# STM32H730_PINOUT.net
KiCad netlist of a schematic drawn in Altium Designer
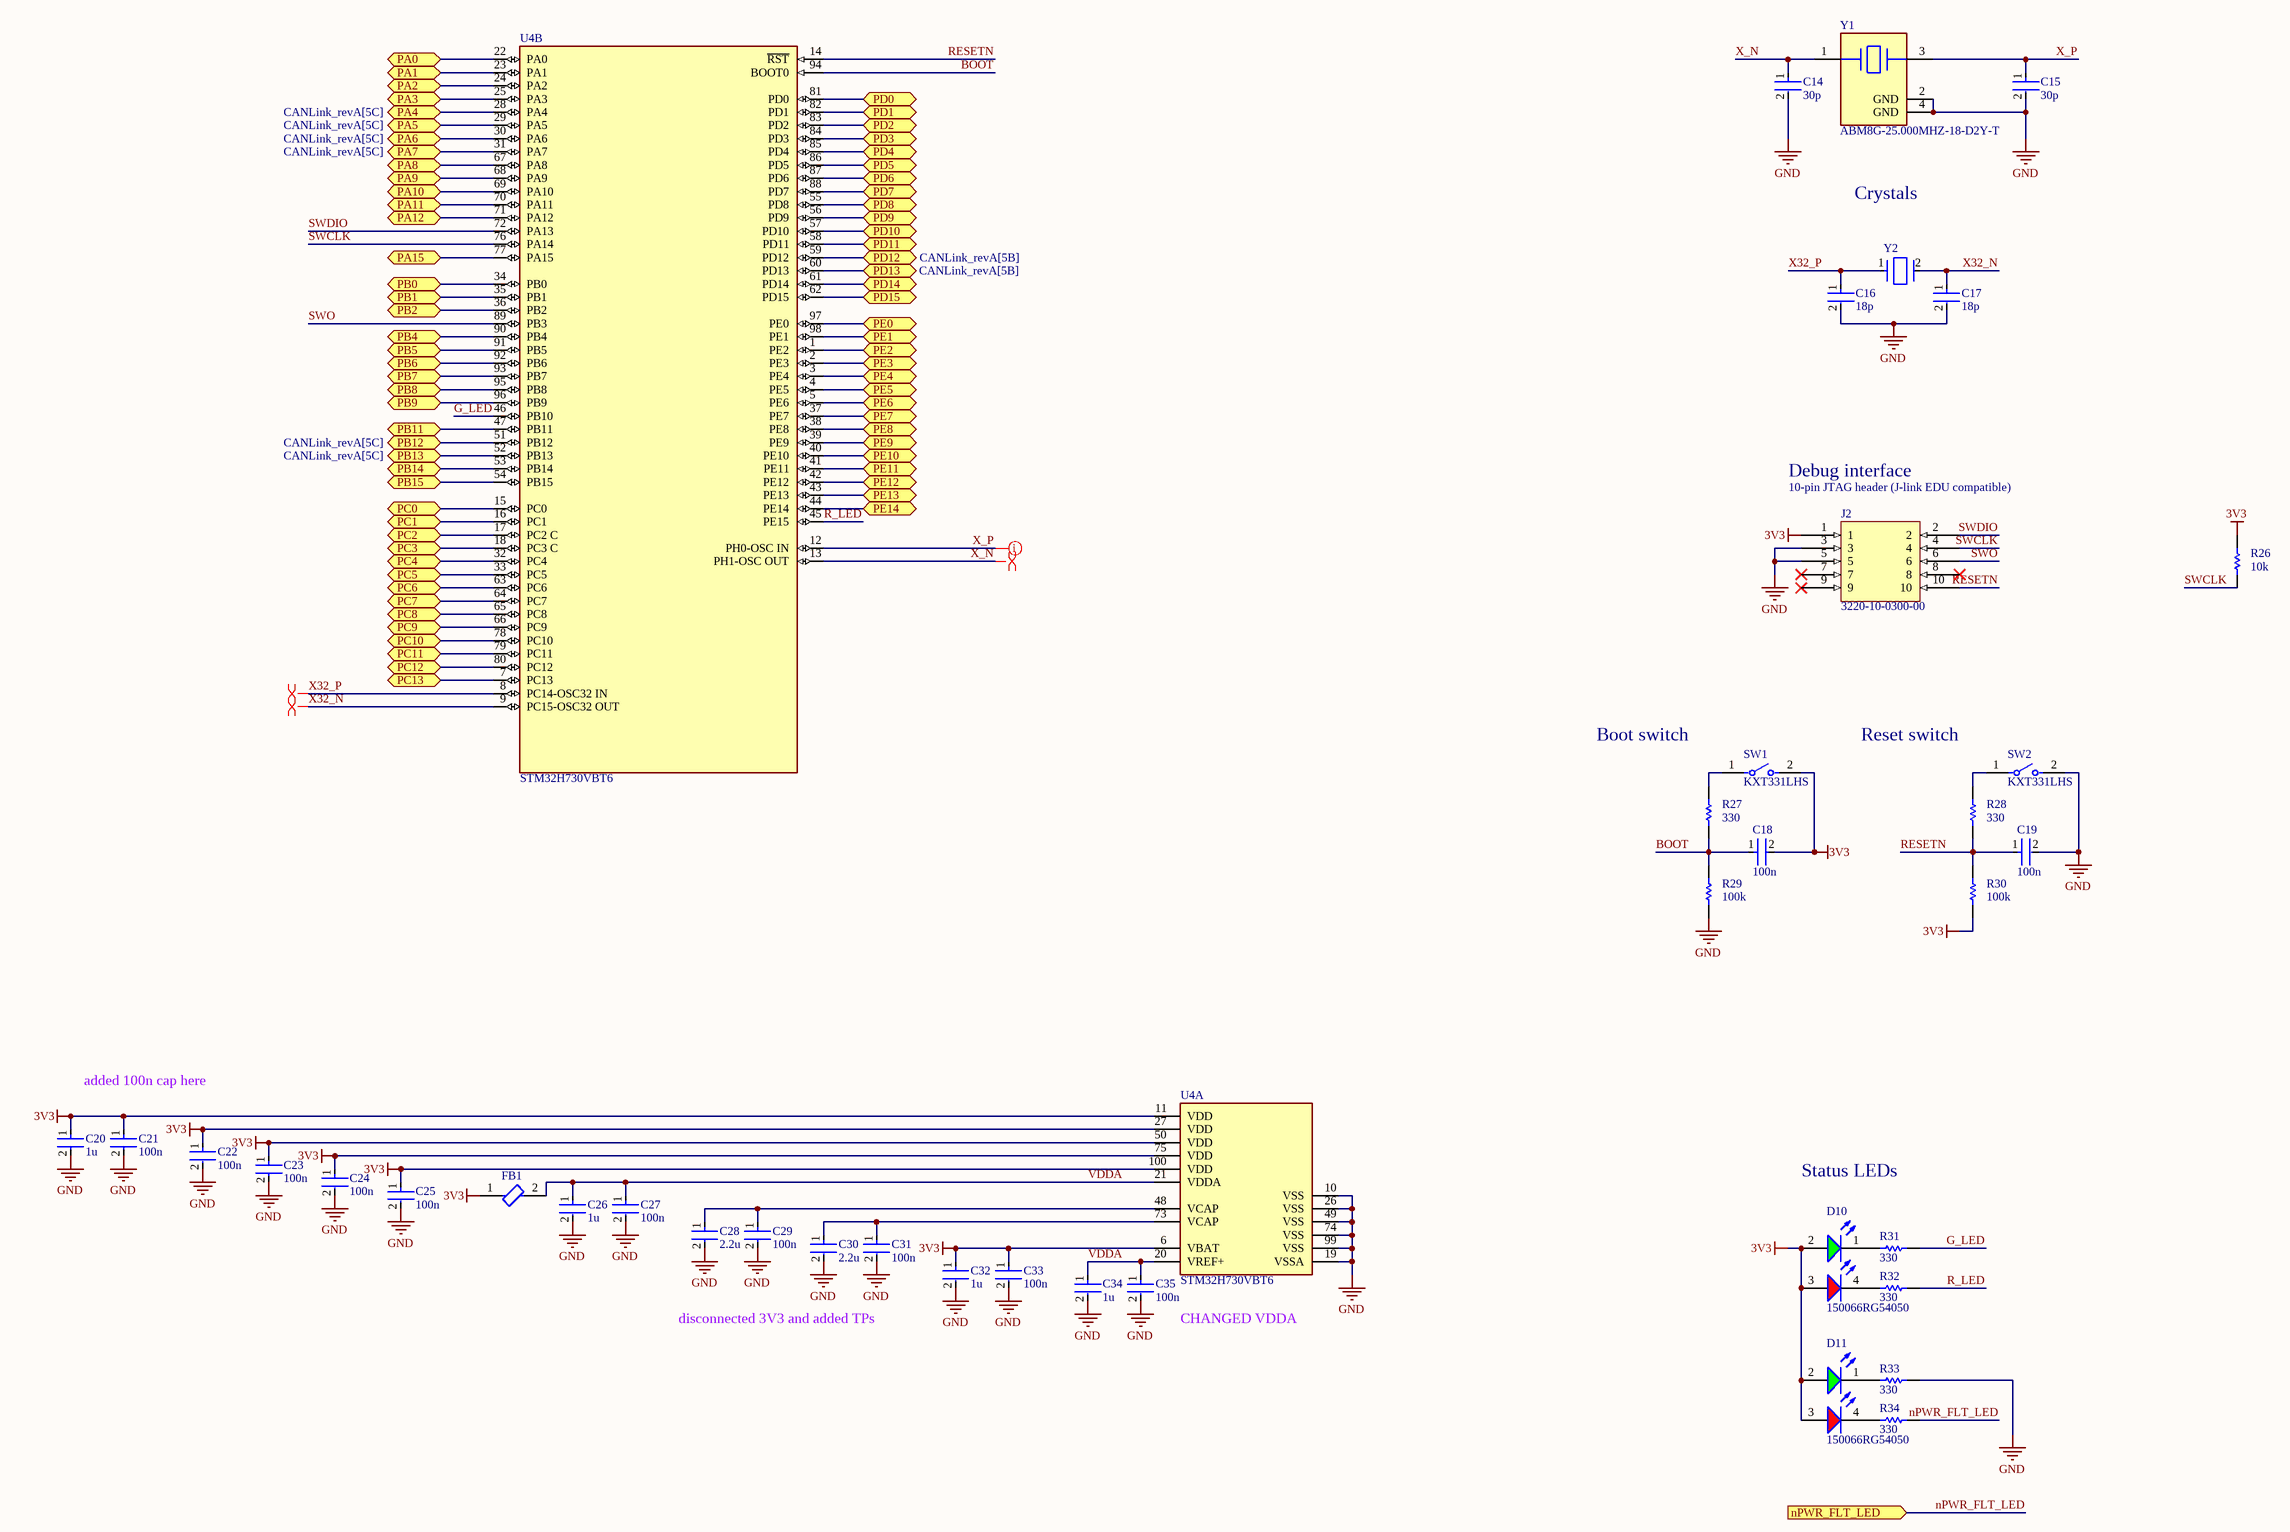
[diagram p0: STM32H730_PINOUT.SchDoc]

(export (version "E")
  (design (tool "Eeschema 10.0.6"))
  (components
    (comp (ref "C14")
      (value "30p")
      (footprint "FP-0402-L_1_0_0_05-W_0_5-IPC_A")
      (description "LARGE PADS, 0402 CAP, CHANGE COMMENT TO MATCH REAL P/N")
      (libsource (lib "Space Concordia") (part "b4654b650e69147ec39a6b967a45e02"))
    )
    (comp (ref "C15")
      (value "30p")
      (footprint "FP-0402-L_1_0_0_05-W_0_5-IPC_A")
      (description "LARGE PADS, 0402 CAP, CHANGE COMMENT TO MATCH REAL P/N")
      (libsource (lib "Space Concordia") (part "b4654b650e69147ec39a6b967a45e02"))
    )
    (comp (ref "C16")
      (value "18p")
      (footprint "FP-0402-L_1_0_0_05-W_0_5-IPC_A")
      (description "LARGE PADS, 0402 CAP, CHANGE COMMENT TO MATCH REAL P/N")
      (libsource (lib "Space Concordia") (part "b4654b650e69147ec39a6b967a45e02"))
    )
    (comp (ref "C17")
      (value "18p")
      (footprint "FP-0402-L_1_0_0_05-W_0_5-IPC_A")
      (description "LARGE PADS, 0402 CAP, CHANGE COMMENT TO MATCH REAL P/N")
      (libsource (lib "Space Concordia") (part "b4654b650e69147ec39a6b967a45e02"))
    )
    (comp (ref "C18")
      (value "100n")
      (footprint "FP-0402-L_1_0_0_05-W_0_5-IPC_A")
      (description "LARGE PADS, 0402 CAP, CHANGE COMMENT TO MATCH REAL P/N")
      (libsource (lib "Space Concordia") (part "b4654b650e69147ec39a6b967a45e02"))
    )
    (comp (ref "C19")
      (value "100n")
      (footprint "FP-0402-L_1_0_0_05-W_0_5-IPC_A")
      (description "LARGE PADS, 0402 CAP, CHANGE COMMENT TO MATCH REAL P/N")
      (libsource (lib "Space Concordia") (part "b4654b650e69147ec39a6b967a45e02"))
    )
    (comp (ref "C20")
      (value "1u")
      (footprint "FP-0402-L_1_0_0_05-W_0_5-IPC_A")
      (description "LARGE PADS, 0402 CAP, CHANGE COMMENT TO MATCH REAL P/N")
      (libsource (lib "Space Concordia") (part "b4654b650e69147ec39a6b967a45e02"))
    )
    (comp (ref "C21")
      (value "100n")
      (footprint "FP-0402-L_1_0_0_05-W_0_5-IPC_A")
      (description "LARGE PADS, 0402 CAP, CHANGE COMMENT TO MATCH REAL P/N")
      (libsource (lib "Space Concordia") (part "b4654b650e69147ec39a6b967a45e02"))
    )
    (comp (ref "C22")
      (value "100n")
      (footprint "FP-0402-L_1_0_0_05-W_0_5-IPC_A")
      (description "LARGE PADS, 0402 CAP, CHANGE COMMENT TO MATCH REAL P/N")
      (libsource (lib "Space Concordia") (part "b4654b650e69147ec39a6b967a45e02"))
    )
    (comp (ref "C23")
      (value "100n")
      (footprint "FP-0402-L_1_0_0_05-W_0_5-IPC_A")
      (description "LARGE PADS, 0402 CAP, CHANGE COMMENT TO MATCH REAL P/N")
      (libsource (lib "Space Concordia") (part "b4654b650e69147ec39a6b967a45e02"))
    )
    (comp (ref "C24")
      (value "100n")
      (footprint "FP-0402-L_1_0_0_05-W_0_5-IPC_A")
      (description "LARGE PADS, 0402 CAP, CHANGE COMMENT TO MATCH REAL P/N")
      (libsource (lib "Space Concordia") (part "b4654b650e69147ec39a6b967a45e02"))
    )
    (comp (ref "C25")
      (value "100n")
      (footprint "FP-0402-L_1_0_0_05-W_0_5-IPC_A")
      (description "LARGE PADS, 0402 CAP, CHANGE COMMENT TO MATCH REAL P/N")
      (libsource (lib "Space Concordia") (part "b4654b650e69147ec39a6b967a45e02"))
    )
    (comp (ref "C26")
      (value "1u")
      (footprint "FP-0402-L_1_0_0_05-W_0_5-IPC_A")
      (description "LARGE PADS, 0402 CAP, CHANGE COMMENT TO MATCH REAL P/N")
      (libsource (lib "Space Concordia") (part "b4654b650e69147ec39a6b967a45e02"))
    )
    (comp (ref "C27")
      (value "100n")
      (footprint "FP-0402-L_1_0_0_05-W_0_5-IPC_A")
      (description "LARGE PADS, 0402 CAP, CHANGE COMMENT TO MATCH REAL P/N")
      (libsource (lib "Space Concordia") (part "b4654b650e69147ec39a6b967a45e02"))
    )
    (comp (ref "C28")
      (value "2.2u")
      (footprint "FP-0402-L_1_0_0_05-W_0_5-IPC_A")
      (description "LARGE PADS, 0402 CAP, CHANGE COMMENT TO MATCH REAL P/N")
      (libsource (lib "Space Concordia") (part "b4654b650e69147ec39a6b967a45e02"))
    )
    (comp (ref "C29")
      (value "100n")
      (footprint "FP-0402-L_1_0_0_05-W_0_5-IPC_A")
      (description "LARGE PADS, 0402 CAP, CHANGE COMMENT TO MATCH REAL P/N")
      (libsource (lib "Space Concordia") (part "b4654b650e69147ec39a6b967a45e02"))
    )
    (comp (ref "C30")
      (value "2.2u")
      (footprint "FP-0402-L_1_0_0_05-W_0_5-IPC_A")
      (description "LARGE PADS, 0402 CAP, CHANGE COMMENT TO MATCH REAL P/N")
      (libsource (lib "Space Concordia") (part "b4654b650e69147ec39a6b967a45e02"))
    )
    (comp (ref "C31")
      (value "100n")
      (footprint "FP-0402-L_1_0_0_05-W_0_5-IPC_A")
      (description "LARGE PADS, 0402 CAP, CHANGE COMMENT TO MATCH REAL P/N")
      (libsource (lib "Space Concordia") (part "b4654b650e69147ec39a6b967a45e02"))
    )
    (comp (ref "C32")
      (value "1u")
      (footprint "FP-0402-L_1_0_0_05-W_0_5-IPC_A")
      (description "LARGE PADS, 0402 CAP, CHANGE COMMENT TO MATCH REAL P/N")
      (libsource (lib "Space Concordia") (part "b4654b650e69147ec39a6b967a45e02"))
    )
    (comp (ref "C33")
      (value "100n")
      (footprint "FP-0402-L_1_0_0_05-W_0_5-IPC_A")
      (description "LARGE PADS, 0402 CAP, CHANGE COMMENT TO MATCH REAL P/N")
      (libsource (lib "Space Concordia") (part "b4654b650e69147ec39a6b967a45e02"))
    )
    (comp (ref "C34")
      (value "1u")
      (footprint "FP-0402-L_1_0_0_05-W_0_5-IPC_A")
      (description "LARGE PADS, 0402 CAP, CHANGE COMMENT TO MATCH REAL P/N")
      (libsource (lib "Space Concordia") (part "b4654b650e69147ec39a6b967a45e02"))
    )
    (comp (ref "C35")
      (value "100n")
      (footprint "FP-0402-L_1_0_0_05-W_0_5-IPC_A")
      (description "LARGE PADS, 0402 CAP, CHANGE COMMENT TO MATCH REAL P/N")
      (libsource (lib "Space Concordia") (part "b4654b650e69147ec39a6b967a45e02"))
    )
    (comp (ref "D10")
      (value "150066RG54050")
      (footprint "WL-SBCD_0606")
      (description "Led, Red/Grn, 180Mcd/230Mcd, 624Nm/525Nm Rohs Compliant: Yes")
      (fields (field (name "SOURCE") "rgled.SchLib"))
      (libsource (lib "Space Concordia") (part "CMP-004-00034-2"))
    )
    (comp (ref "D11")
      (value "150066RG54050")
      (footprint "WL-SBCD_0606")
      (description "Led, Red/Grn, 180Mcd/230Mcd, 624Nm/525Nm Rohs Compliant: Yes")
      (fields (field (name "SOURCE") "rgled.SchLib"))
      (libsource (lib "Space Concordia") (part "CMP-004-00034-2"))
    )
    (comp (ref "FB1")
      (value "BLM15PX601SN1D")
      (footprint "FP-BLM15-0_05-IPC_A")
      (description "Chip Ferrite Bead, 0402, 600Ω @ 100MHz, 0.23Ω, 25%, 900mA")
      (fields (field (name "TOLERANCE") "25%"))
      (libsource (lib "Altium Content Vault") (part "5f30dd21d616792df468990f7003faa"))
    )
    (comp (ref "J2")
      (value "3220-10-0300-00")
      (footprint "3220-10-0300-00-Footprint-1")
      (description "CONN HEADER SMD 10POS 1.27MM")
      (libsource (lib "Space Concordia") (part "3220-10-0300-00"))
    )
    (comp (ref "R26")
      (value "10k")
      (footprint "R0603B")
      (description "Resistor")
      (libsource (lib "Space Concordia") (part "Resistor"))
    )
    (comp (ref "R27")
      (value "330")
      (footprint "R0603B")
      (description "Resistor")
      (libsource (lib "Space Concordia") (part "Resistor"))
    )
    (comp (ref "R28")
      (value "330")
      (footprint "R0603B")
      (description "Resistor")
      (libsource (lib "Space Concordia") (part "Resistor"))
    )
    (comp (ref "R29")
      (value "100k")
      (footprint "R0603B")
      (description "Resistor")
      (libsource (lib "Space Concordia") (part "Resistor"))
    )
    (comp (ref "R30")
      (value "100k")
      (footprint "R0603B")
      (description "Resistor")
      (libsource (lib "Space Concordia") (part "Resistor"))
    )
    (comp (ref "R31")
      (value "330")
      (footprint "R0603B")
      (description "Resistor")
      (libsource (lib "Space Concordia") (part "Resistor"))
    )
    (comp (ref "R32")
      (value "330")
      (footprint "R0603B")
      (description "Resistor")
      (libsource (lib "Space Concordia") (part "Resistor"))
    )
    (comp (ref "R33")
      (value "330")
      (footprint "R0603B")
      (description "Resistor")
      (libsource (lib "Space Concordia") (part "Resistor"))
    )
    (comp (ref "R34")
      (value "330")
      (footprint "R0603B")
      (description "Resistor")
      (libsource (lib "Space Concordia") (part "Resistor"))
    )
    (comp (ref "SW1")
      (value "KXT331LHS")
      (footprint "FP-KXT331LHS-MFG")
      (description "SWITCH TACTILE SPST-NO 0.02A 15V")
      (libsource (lib "Altium Content Vault") (part "bb27bde45df87f1f469753f287ef5ae"))
    )
    (comp (ref "SW2")
      (value "KXT331LHS")
      (footprint "FP-KXT331LHS-MFG")
      (description "SWITCH TACTILE SPST-NO 0.02A 15V")
      (libsource (lib "Altium Content Vault") (part "bb27bde45df87f1f469753f287ef5ae"))
    )
    (comp (ref "U4")
      (value "STM32H730VBT6")
      (footprint "FP-LQFP100-1L-IPC_C")
      (description "IC MCU 32BIT 128KB FLASH 100LQFP")
      (libsource (lib "Altium Content Vault") (part "44dc6501260a4d92b846760feb66c20"))
    )
    (comp (ref "Y1")
      (value "ABM8G-25.000MHZ-18-D2Y-T")
      (footprint "FP-ABM8G-MFG")
      (description "Crystal 25MHz ±20ppm (Tol) ±30ppm (Stability) 18pF FUND 60Ω 4-Pin SMD T/R")
      (fields (field (name "TOLERANCE") "20ppm"))
      (libsource (lib "Altium Content Vault") (part "48e526d86b7f2615d98721063c72f49"))
    )
    (comp (ref "Y2")
      (value "ECS-.327-12.5-1210-TR")
      (footprint "FP-ECX-1210-MFG")
      (description "CRYSTAL 32.7680KHZ 12.5PF SMD")
      (fields
        (field (name "OCTOPART") "https://octopart.com/ecs-.327-12.5-1210-tr-ecs+international-81221340")
        (field (name "TOLERANCE") "20ppm")
      )
      (libsource (lib "Altium Content Vault") (part "99724985039315a44fd0d1401b84e49"))
    )
  )
  (nets
    (net (code "1") (name "/BOOT") (class "Default")
      (node (ref "C18") (pin "1") (pinfunction "1_1") (pintype "passive"))
      (node (ref "R27") (pin "1") (pinfunction "1_1") (pintype "passive"))
      (node (ref "R29") (pin "2") (pinfunction "2_2") (pintype "passive"))
      (node (ref "U4") (pin "94") (pinfunction "BOOT0_94") (pintype "input"))
    )
    (net (code "2") (name "/G_LED") (class "Default")
      (node (ref "R31") (pin "1") (pinfunction "1_1") (pintype "passive"))
      (node (ref "U4") (pin "46") (pinfunction "PB10_46") (pintype "bidirectional"))
    )
    (net (code "3") (name "/PA0") (class "Default")
      (node (ref "U4") (pin "22") (pinfunction "PA0_22") (pintype "bidirectional"))
    )
    (net (code "4") (name "/PA1") (class "Default")
      (node (ref "U4") (pin "23") (pinfunction "PA1_23") (pintype "bidirectional"))
    )
    (net (code "5") (name "/PA2") (class "Default")
      (node (ref "U4") (pin "24") (pinfunction "PA2_24") (pintype "bidirectional"))
    )
    (net (code "6") (name "/PA3") (class "Default")
      (node (ref "U4") (pin "25") (pinfunction "PA3_25") (pintype "bidirectional"))
    )
    (net (code "7") (name "/PA4") (class "Default")
      (node (ref "U4") (pin "28") (pinfunction "PA4_28") (pintype "bidirectional"))
    )
    (net (code "8") (name "/PA5") (class "Default")
      (node (ref "U4") (pin "29") (pinfunction "PA5_29") (pintype "bidirectional"))
    )
    (net (code "9") (name "/PA6") (class "Default")
      (node (ref "U4") (pin "30") (pinfunction "PA6_30") (pintype "bidirectional"))
    )
    (net (code "10") (name "/PA7") (class "Default")
      (node (ref "U4") (pin "31") (pinfunction "PA7_31") (pintype "bidirectional"))
    )
    (net (code "11") (name "/PA8") (class "Default")
      (node (ref "U4") (pin "67") (pinfunction "PA8_67") (pintype "bidirectional"))
    )
    (net (code "12") (name "/PA9") (class "Default")
      (node (ref "U4") (pin "68") (pinfunction "PA9_68") (pintype "bidirectional"))
    )
    (net (code "13") (name "/PA10") (class "Default")
      (node (ref "U4") (pin "69") (pinfunction "PA10_69") (pintype "bidirectional"))
    )
    (net (code "14") (name "/PA11") (class "Default")
      (node (ref "U4") (pin "70") (pinfunction "PA11_70") (pintype "bidirectional"))
    )
    (net (code "15") (name "/PA12") (class "Default")
      (node (ref "U4") (pin "71") (pinfunction "PA12_71") (pintype "bidirectional"))
    )
    (net (code "16") (name "/PA15") (class "Default")
      (node (ref "U4") (pin "77") (pinfunction "PA15_77") (pintype "bidirectional"))
    )
    (net (code "17") (name "/PB0") (class "Default")
      (node (ref "U4") (pin "34") (pinfunction "PB0_34") (pintype "bidirectional"))
    )
    (net (code "18") (name "/PB1") (class "Default")
      (node (ref "U4") (pin "35") (pinfunction "PB1_35") (pintype "bidirectional"))
    )
    (net (code "19") (name "/PB2") (class "Default")
      (node (ref "U4") (pin "36") (pinfunction "PB2_36") (pintype "bidirectional"))
    )
    (net (code "20") (name "/PB4") (class "Default")
      (node (ref "U4") (pin "90") (pinfunction "PB4_90") (pintype "bidirectional"))
    )
    (net (code "21") (name "/PB5") (class "Default")
      (node (ref "U4") (pin "91") (pinfunction "PB5_91") (pintype "bidirectional"))
    )
    (net (code "22") (name "/PB6") (class "Default")
      (node (ref "U4") (pin "92") (pinfunction "PB6_92") (pintype "bidirectional"))
    )
    (net (code "23") (name "/PB7") (class "Default")
      (node (ref "U4") (pin "93") (pinfunction "PB7_93") (pintype "bidirectional"))
    )
    (net (code "24") (name "/PB8") (class "Default")
      (node (ref "U4") (pin "95") (pinfunction "PB8_95") (pintype "bidirectional"))
    )
    (net (code "25") (name "/PB9") (class "Default")
      (node (ref "U4") (pin "96") (pinfunction "PB9_96") (pintype "bidirectional"))
    )
    (net (code "26") (name "/PB11") (class "Default")
      (node (ref "U4") (pin "47") (pinfunction "PB11_47") (pintype "bidirectional"))
    )
    (net (code "27") (name "/PB12") (class "Default")
      (node (ref "U4") (pin "51") (pinfunction "PB12_51") (pintype "bidirectional"))
    )
    (net (code "28") (name "/PB13") (class "Default")
      (node (ref "U4") (pin "52") (pinfunction "PB13_52") (pintype "bidirectional"))
    )
    (net (code "29") (name "/PB14") (class "Default")
      (node (ref "U4") (pin "53") (pinfunction "PB14_53") (pintype "bidirectional"))
    )
    (net (code "30") (name "/PB15") (class "Default")
      (node (ref "U4") (pin "54") (pinfunction "PB15_54") (pintype "bidirectional"))
    )
    (net (code "31") (name "/PC0") (class "Default")
      (node (ref "U4") (pin "15") (pinfunction "PC0_15") (pintype "bidirectional"))
    )
    (net (code "32") (name "/PC1") (class "Default")
      (node (ref "U4") (pin "16") (pinfunction "PC1_16") (pintype "bidirectional"))
    )
    (net (code "33") (name "/PC2") (class "Default")
      (node (ref "U4") (pin "17") (pinfunction "PC2_C_17") (pintype "bidirectional"))
    )
    (net (code "34") (name "/PC3") (class "Default")
      (node (ref "U4") (pin "18") (pinfunction "PC3_C_18") (pintype "bidirectional"))
    )
    (net (code "35") (name "/PC4") (class "Default")
      (node (ref "U4") (pin "32") (pinfunction "PC4_32") (pintype "bidirectional"))
    )
    (net (code "36") (name "/PC5") (class "Default")
      (node (ref "U4") (pin "33") (pinfunction "PC5_33") (pintype "bidirectional"))
    )
    (net (code "37") (name "/PC6") (class "Default")
      (node (ref "U4") (pin "63") (pinfunction "PC6_63") (pintype "bidirectional"))
    )
    (net (code "38") (name "/PC7") (class "Default")
      (node (ref "U4") (pin "64") (pinfunction "PC7_64") (pintype "bidirectional"))
    )
    (net (code "39") (name "/PC8") (class "Default")
      (node (ref "U4") (pin "65") (pinfunction "PC8_65") (pintype "bidirectional"))
    )
    (net (code "40") (name "/PC9") (class "Default")
      (node (ref "U4") (pin "66") (pinfunction "PC9_66") (pintype "bidirectional"))
    )
    (net (code "41") (name "/PC10") (class "Default")
      (node (ref "U4") (pin "78") (pinfunction "PC10_78") (pintype "bidirectional"))
    )
    (net (code "42") (name "/PC11") (class "Default")
      (node (ref "U4") (pin "79") (pinfunction "PC11_79") (pintype "bidirectional"))
    )
    (net (code "43") (name "/PC12") (class "Default")
      (node (ref "U4") (pin "80") (pinfunction "PC12_80") (pintype "bidirectional"))
    )
    (net (code "44") (name "/PC13") (class "Default")
      (node (ref "U4") (pin "7") (pinfunction "PC13_7") (pintype "bidirectional"))
    )
    (net (code "45") (name "/PD0") (class "Default")
      (node (ref "U4") (pin "81") (pinfunction "PD0_81") (pintype "bidirectional"))
    )
    (net (code "46") (name "/PD1") (class "Default")
      (node (ref "U4") (pin "82") (pinfunction "PD1_82") (pintype "bidirectional"))
    )
    (net (code "47") (name "/PD2") (class "Default")
      (node (ref "U4") (pin "83") (pinfunction "PD2_83") (pintype "bidirectional"))
    )
    (net (code "48") (name "/PD3") (class "Default")
      (node (ref "U4") (pin "84") (pinfunction "PD3_84") (pintype "bidirectional"))
    )
    (net (code "49") (name "/PD4") (class "Default")
      (node (ref "U4") (pin "85") (pinfunction "PD4_85") (pintype "bidirectional"))
    )
    (net (code "50") (name "/PD5") (class "Default")
      (node (ref "U4") (pin "86") (pinfunction "PD5_86") (pintype "bidirectional"))
    )
    (net (code "51") (name "/PD6") (class "Default")
      (node (ref "U4") (pin "87") (pinfunction "PD6_87") (pintype "bidirectional"))
    )
    (net (code "52") (name "/PD7") (class "Default")
      (node (ref "U4") (pin "88") (pinfunction "PD7_88") (pintype "bidirectional"))
    )
    (net (code "53") (name "/PD8") (class "Default")
      (node (ref "U4") (pin "55") (pinfunction "PD8_55") (pintype "bidirectional"))
    )
    (net (code "54") (name "/PD9") (class "Default")
      (node (ref "U4") (pin "56") (pinfunction "PD9_56") (pintype "bidirectional"))
    )
    (net (code "55") (name "/PD10") (class "Default")
      (node (ref "U4") (pin "57") (pinfunction "PD10_57") (pintype "bidirectional"))
    )
    (net (code "56") (name "/PD11") (class "Default")
      (node (ref "U4") (pin "58") (pinfunction "PD11_58") (pintype "bidirectional"))
    )
    (net (code "57") (name "/PD12") (class "Default")
      (node (ref "U4") (pin "59") (pinfunction "PD12_59") (pintype "bidirectional"))
    )
    (net (code "58") (name "/PD13") (class "Default")
      (node (ref "U4") (pin "60") (pinfunction "PD13_60") (pintype "bidirectional"))
    )
    (net (code "59") (name "/PD14") (class "Default")
      (node (ref "U4") (pin "61") (pinfunction "PD14_61") (pintype "bidirectional"))
    )
    (net (code "60") (name "/PD15") (class "Default")
      (node (ref "U4") (pin "62") (pinfunction "PD15_62") (pintype "bidirectional"))
    )
    (net (code "61") (name "/PE0") (class "Default")
      (node (ref "U4") (pin "97") (pinfunction "PE0_97") (pintype "bidirectional"))
    )
    (net (code "62") (name "/PE1") (class "Default")
      (node (ref "U4") (pin "98") (pinfunction "PE1_98") (pintype "bidirectional"))
    )
    (net (code "63") (name "/PE2") (class "Default")
      (node (ref "U4") (pin "1") (pinfunction "PE2_1") (pintype "bidirectional"))
    )
    (net (code "64") (name "/PE3") (class "Default")
      (node (ref "U4") (pin "2") (pinfunction "PE3_2") (pintype "bidirectional"))
    )
    (net (code "65") (name "/PE4") (class "Default")
      (node (ref "U4") (pin "3") (pinfunction "PE4_3") (pintype "bidirectional"))
    )
    (net (code "66") (name "/PE5") (class "Default")
      (node (ref "U4") (pin "4") (pinfunction "PE5_4") (pintype "bidirectional"))
    )
    (net (code "67") (name "/PE6") (class "Default")
      (node (ref "U4") (pin "5") (pinfunction "PE6_5") (pintype "bidirectional"))
    )
    (net (code "68") (name "/PE7") (class "Default")
      (node (ref "U4") (pin "37") (pinfunction "PE7_37") (pintype "bidirectional"))
    )
    (net (code "69") (name "/PE8") (class "Default")
      (node (ref "U4") (pin "38") (pinfunction "PE8_38") (pintype "bidirectional"))
    )
    (net (code "70") (name "/PE9") (class "Default")
      (node (ref "U4") (pin "39") (pinfunction "PE9_39") (pintype "bidirectional"))
    )
    (net (code "71") (name "/PE10") (class "Default")
      (node (ref "U4") (pin "40") (pinfunction "PE10_40") (pintype "bidirectional"))
    )
    (net (code "72") (name "/PE11") (class "Default")
      (node (ref "U4") (pin "41") (pinfunction "PE11_41") (pintype "bidirectional"))
    )
    (net (code "73") (name "/PE12") (class "Default")
      (node (ref "U4") (pin "42") (pinfunction "PE12_42") (pintype "bidirectional"))
    )
    (net (code "74") (name "/PE13") (class "Default")
      (node (ref "U4") (pin "43") (pinfunction "PE13_43") (pintype "bidirectional"))
    )
    (net (code "75") (name "/PE14") (class "Default")
      (node (ref "U4") (pin "44") (pinfunction "PE14_44") (pintype "bidirectional"))
    )
    (net (code "76") (name "/RESETN") (class "Default")
      (node (ref "C19") (pin "1") (pinfunction "1_1") (pintype "passive"))
      (node (ref "J2") (pin "10") (pinfunction "10_10") (pintype "input"))
      (node (ref "R28") (pin "1") (pinfunction "1_1") (pintype "passive"))
      (node (ref "R30") (pin "2") (pinfunction "2_2") (pintype "passive"))
      (node (ref "U4") (pin "14") (pinfunction "~{RST}_14") (pintype "input"))
    )
    (net (code "77") (name "/R_LED") (class "Default")
      (node (ref "R32") (pin "1") (pinfunction "1_1") (pintype "passive"))
      (node (ref "U4") (pin "45") (pinfunction "PE15_45") (pintype "bidirectional"))
    )
    (net (code "78") (name "/SWCLK") (class "Default")
      (node (ref "J2") (pin "4") (pinfunction "4_4") (pintype "input"))
      (node (ref "R26") (pin "1") (pinfunction "1_1") (pintype "passive"))
      (node (ref "U4") (pin "76") (pinfunction "PA14_76") (pintype "bidirectional"))
    )
    (net (code "79") (name "/SWDIO") (class "Default")
      (node (ref "J2") (pin "2") (pinfunction "2_2") (pintype "input"))
      (node (ref "U4") (pin "72") (pinfunction "PA13_72") (pintype "bidirectional"))
    )
    (net (code "80") (name "/SWO") (class "Default")
      (node (ref "J2") (pin "6") (pinfunction "6_6") (pintype "input"))
      (node (ref "U4") (pin "89") (pinfunction "PB3_89") (pintype "bidirectional"))
    )
    (net (code "81") (name "/VDDA") (class "Default")
      (node (ref "C26") (pin "1") (pinfunction "1_1") (pintype "passive"))
      (node (ref "C27") (pin "1") (pinfunction "1_1") (pintype "passive"))
      (node (ref "C34") (pin "1") (pinfunction "1_1") (pintype "passive"))
      (node (ref "C35") (pin "1") (pinfunction "1_1") (pintype "passive"))
      (node (ref "FB1") (pin "2") (pinfunction "2_2") (pintype "passive"))
      (node (ref "U4") (pin "20") (pinfunction "VREF+_20") (pintype "power_in"))
      (node (ref "U4") (pin "21") (pinfunction "VDDA_21") (pintype "power_in"))
    )
    (net (code "82") (name "/X32_N") (class "Default")
      (node (ref "C17") (pin "1") (pinfunction "1_1") (pintype "passive"))
      (node (ref "U4") (pin "9") (pinfunction "PC15-OSC32_OUT_9") (pintype "bidirectional"))
      (node (ref "Y2") (pin "2") (pinfunction "Out/In_2") (pintype "passive"))
    )
    (net (code "83") (name "/X32_P") (class "Default")
      (node (ref "C16") (pin "1") (pinfunction "1_1") (pintype "passive"))
      (node (ref "U4") (pin "8") (pinfunction "PC14-OSC32_IN_8") (pintype "bidirectional"))
      (node (ref "Y2") (pin "1") (pinfunction "In/Out_1") (pintype "passive"))
    )
    (net (code "84") (name "/X_N") (class "Default")
      (node (ref "C14") (pin "1") (pinfunction "1_1") (pintype "passive"))
      (node (ref "U4") (pin "13") (pinfunction "PH1-OSC_OUT_13") (pintype "bidirectional"))
      (node (ref "Y1") (pin "1") (pinfunction "1_1") (pintype "passive"))
    )
    (net (code "85") (name "/X_P") (class "Default")
      (node (ref "C15") (pin "1") (pinfunction "1_1") (pintype "passive"))
      (node (ref "U4") (pin "12") (pinfunction "PH0-OSC_IN_12") (pintype "bidirectional"))
      (node (ref "Y1") (pin "3") (pinfunction "3_3") (pintype "passive"))
    )
    (net (code "86") (name "/nPWR_FLT_LED") (class "Default")
      (node (ref "R34") (pin "1") (pinfunction "1_1") (pintype "passive"))
    )
    (net (code "87") (name "3V3") (class "Default")
      (node (ref "C18") (pin "2") (pinfunction "2_2") (pintype "passive"))
      (node (ref "C20") (pin "1") (pinfunction "1_1") (pintype "passive"))
      (node (ref "C21") (pin "1") (pinfunction "1_1") (pintype "passive"))
      (node (ref "C22") (pin "1") (pinfunction "1_1") (pintype "passive"))
      (node (ref "C23") (pin "1") (pinfunction "1_1") (pintype "passive"))
      (node (ref "C24") (pin "1") (pinfunction "1_1") (pintype "passive"))
      (node (ref "C25") (pin "1") (pinfunction "1_1") (pintype "passive"))
      (node (ref "C32") (pin "1") (pinfunction "1_1") (pintype "passive"))
      (node (ref "C33") (pin "1") (pinfunction "1_1") (pintype "passive"))
      (node (ref "D10") (pin "2") (pinfunction "A_2") (pintype "passive"))
      (node (ref "D10") (pin "3") (pinfunction "A_3") (pintype "passive"))
      (node (ref "D11") (pin "2") (pinfunction "A_2") (pintype "passive"))
      (node (ref "D11") (pin "3") (pinfunction "A_3") (pintype "passive"))
      (node (ref "FB1") (pin "1") (pinfunction "1_1") (pintype "passive"))
      (node (ref "J2") (pin "1") (pinfunction "1_1") (pintype "input"))
      (node (ref "R26") (pin "2") (pinfunction "2_2") (pintype "passive"))
      (node (ref "R30") (pin "1") (pinfunction "1_1") (pintype "passive"))
      (node (ref "SW1") (pin "2") (pinfunction "2_2") (pintype "passive"))
      (node (ref "U4") (pin "100") (pinfunction "VDD_100") (pintype "power_in"))
      (node (ref "U4") (pin "11") (pinfunction "VDD_11") (pintype "power_in"))
      (node (ref "U4") (pin "27") (pinfunction "VDD_27") (pintype "power_in"))
      (node (ref "U4") (pin "50") (pinfunction "VDD_50") (pintype "power_in"))
      (node (ref "U4") (pin "6") (pinfunction "VBAT_6") (pintype "power_in"))
      (node (ref "U4") (pin "75") (pinfunction "VDD_75") (pintype "power_in"))
    )
    (net (code "88") (name "GND") (class "Default")
      (node (ref "C14") (pin "2") (pinfunction "2_2") (pintype "passive"))
      (node (ref "C15") (pin "2") (pinfunction "2_2") (pintype "passive"))
      (node (ref "C16") (pin "2") (pinfunction "2_2") (pintype "passive"))
      (node (ref "C17") (pin "2") (pinfunction "2_2") (pintype "passive"))
      (node (ref "C19") (pin "2") (pinfunction "2_2") (pintype "passive"))
      (node (ref "C20") (pin "2") (pinfunction "2_2") (pintype "passive"))
      (node (ref "C21") (pin "2") (pinfunction "2_2") (pintype "passive"))
      (node (ref "C22") (pin "2") (pinfunction "2_2") (pintype "passive"))
      (node (ref "C23") (pin "2") (pinfunction "2_2") (pintype "passive"))
      (node (ref "C24") (pin "2") (pinfunction "2_2") (pintype "passive"))
      (node (ref "C25") (pin "2") (pinfunction "2_2") (pintype "passive"))
      (node (ref "C26") (pin "2") (pinfunction "2_2") (pintype "passive"))
      (node (ref "C27") (pin "2") (pinfunction "2_2") (pintype "passive"))
      (node (ref "C28") (pin "2") (pinfunction "2_2") (pintype "passive"))
      (node (ref "C29") (pin "2") (pinfunction "2_2") (pintype "passive"))
      (node (ref "C30") (pin "2") (pinfunction "2_2") (pintype "passive"))
      (node (ref "C31") (pin "2") (pinfunction "2_2") (pintype "passive"))
      (node (ref "C32") (pin "2") (pinfunction "2_2") (pintype "passive"))
      (node (ref "C33") (pin "2") (pinfunction "2_2") (pintype "passive"))
      (node (ref "C34") (pin "2") (pinfunction "2_2") (pintype "passive"))
      (node (ref "C35") (pin "2") (pinfunction "2_2") (pintype "passive"))
      (node (ref "J2") (pin "3") (pinfunction "3_3") (pintype "input"))
      (node (ref "J2") (pin "5") (pinfunction "5_5") (pintype "input"))
      (node (ref "R29") (pin "1") (pinfunction "1_1") (pintype "passive"))
      (node (ref "R33") (pin "1") (pinfunction "1_1") (pintype "passive"))
      (node (ref "SW2") (pin "2") (pinfunction "2_2") (pintype "passive"))
      (node (ref "U4") (pin "10") (pinfunction "VSS_10") (pintype "power_in"))
      (node (ref "U4") (pin "19") (pinfunction "VSSA_19") (pintype "power_in"))
      (node (ref "U4") (pin "26") (pinfunction "VSS_26") (pintype "power_in"))
      (node (ref "U4") (pin "49") (pinfunction "VSS_49") (pintype "power_in"))
      (node (ref "U4") (pin "74") (pinfunction "VSS_74") (pintype "power_in"))
      (node (ref "U4") (pin "99") (pinfunction "VSS_99") (pintype "power_in"))
      (node (ref "Y1") (pin "2") (pinfunction "GND_2") (pintype "power_in"))
      (node (ref "Y1") (pin "4") (pinfunction "GND_4") (pintype "power_in"))
    )
    (net (code "89") (name "Net-(C28-Pad1)") (class "Default")
      (node (ref "C28") (pin "1") (pinfunction "1_1") (pintype "passive"))
      (node (ref "C29") (pin "1") (pinfunction "1_1") (pintype "passive"))
      (node (ref "U4") (pin "48") (pinfunction "VCAP_48") (pintype "power_in"))
    )
    (net (code "90") (name "Net-(C30-Pad1)") (class "Default")
      (node (ref "C30") (pin "1") (pinfunction "1_1") (pintype "passive"))
      (node (ref "C31") (pin "1") (pinfunction "1_1") (pintype "passive"))
      (node (ref "U4") (pin "73") (pinfunction "VCAP_73") (pintype "power_in"))
    )
    (net (code "91") (name "Net-(D10-K-Pad1)") (class "Default")
      (node (ref "D10") (pin "1") (pinfunction "K_1") (pintype "passive"))
      (node (ref "R31") (pin "2") (pinfunction "2_2") (pintype "passive"))
    )
    (net (code "92") (name "Net-(D10-K-Pad4)") (class "Default")
      (node (ref "D10") (pin "4") (pinfunction "K_4") (pintype "passive"))
      (node (ref "R32") (pin "2") (pinfunction "2_2") (pintype "passive"))
    )
    (net (code "93") (name "Net-(D11-K-Pad1)") (class "Default")
      (node (ref "D11") (pin "1") (pinfunction "K_1") (pintype "passive"))
      (node (ref "R33") (pin "2") (pinfunction "2_2") (pintype "passive"))
    )
    (net (code "94") (name "Net-(D11-K-Pad4)") (class "Default")
      (node (ref "D11") (pin "4") (pinfunction "K_4") (pintype "passive"))
      (node (ref "R34") (pin "2") (pinfunction "2_2") (pintype "passive"))
    )
    (net (code "95") (name "Net-(R27-Pad2)") (class "Default")
      (node (ref "R27") (pin "2") (pinfunction "2_2") (pintype "passive"))
      (node (ref "SW1") (pin "1") (pinfunction "1_1") (pintype "passive"))
    )
    (net (code "96") (name "Net-(R28-Pad2)") (class "Default")
      (node (ref "R28") (pin "2") (pinfunction "2_2") (pintype "passive"))
      (node (ref "SW2") (pin "1") (pinfunction "1_1") (pintype "passive"))
    )
    (net (code "97") (name "unconnected-(J2-Pad7)") (class "Default")
      (node (ref "J2") (pin "7") (pinfunction "7_7") (pintype "input+no_connect"))
    )
    (net (code "98") (name "unconnected-(J2-Pad8)") (class "Default")
      (node (ref "J2") (pin "8") (pinfunction "8_8") (pintype "input+no_connect"))
    )
    (net (code "99") (name "unconnected-(J2-Pad9)") (class "Default")
      (node (ref "J2") (pin "9") (pinfunction "9_9") (pintype "input+no_connect"))
    )
  )
)
